# i27_adapt.net
KiCad netlist of a schematic drawn in EAGLE
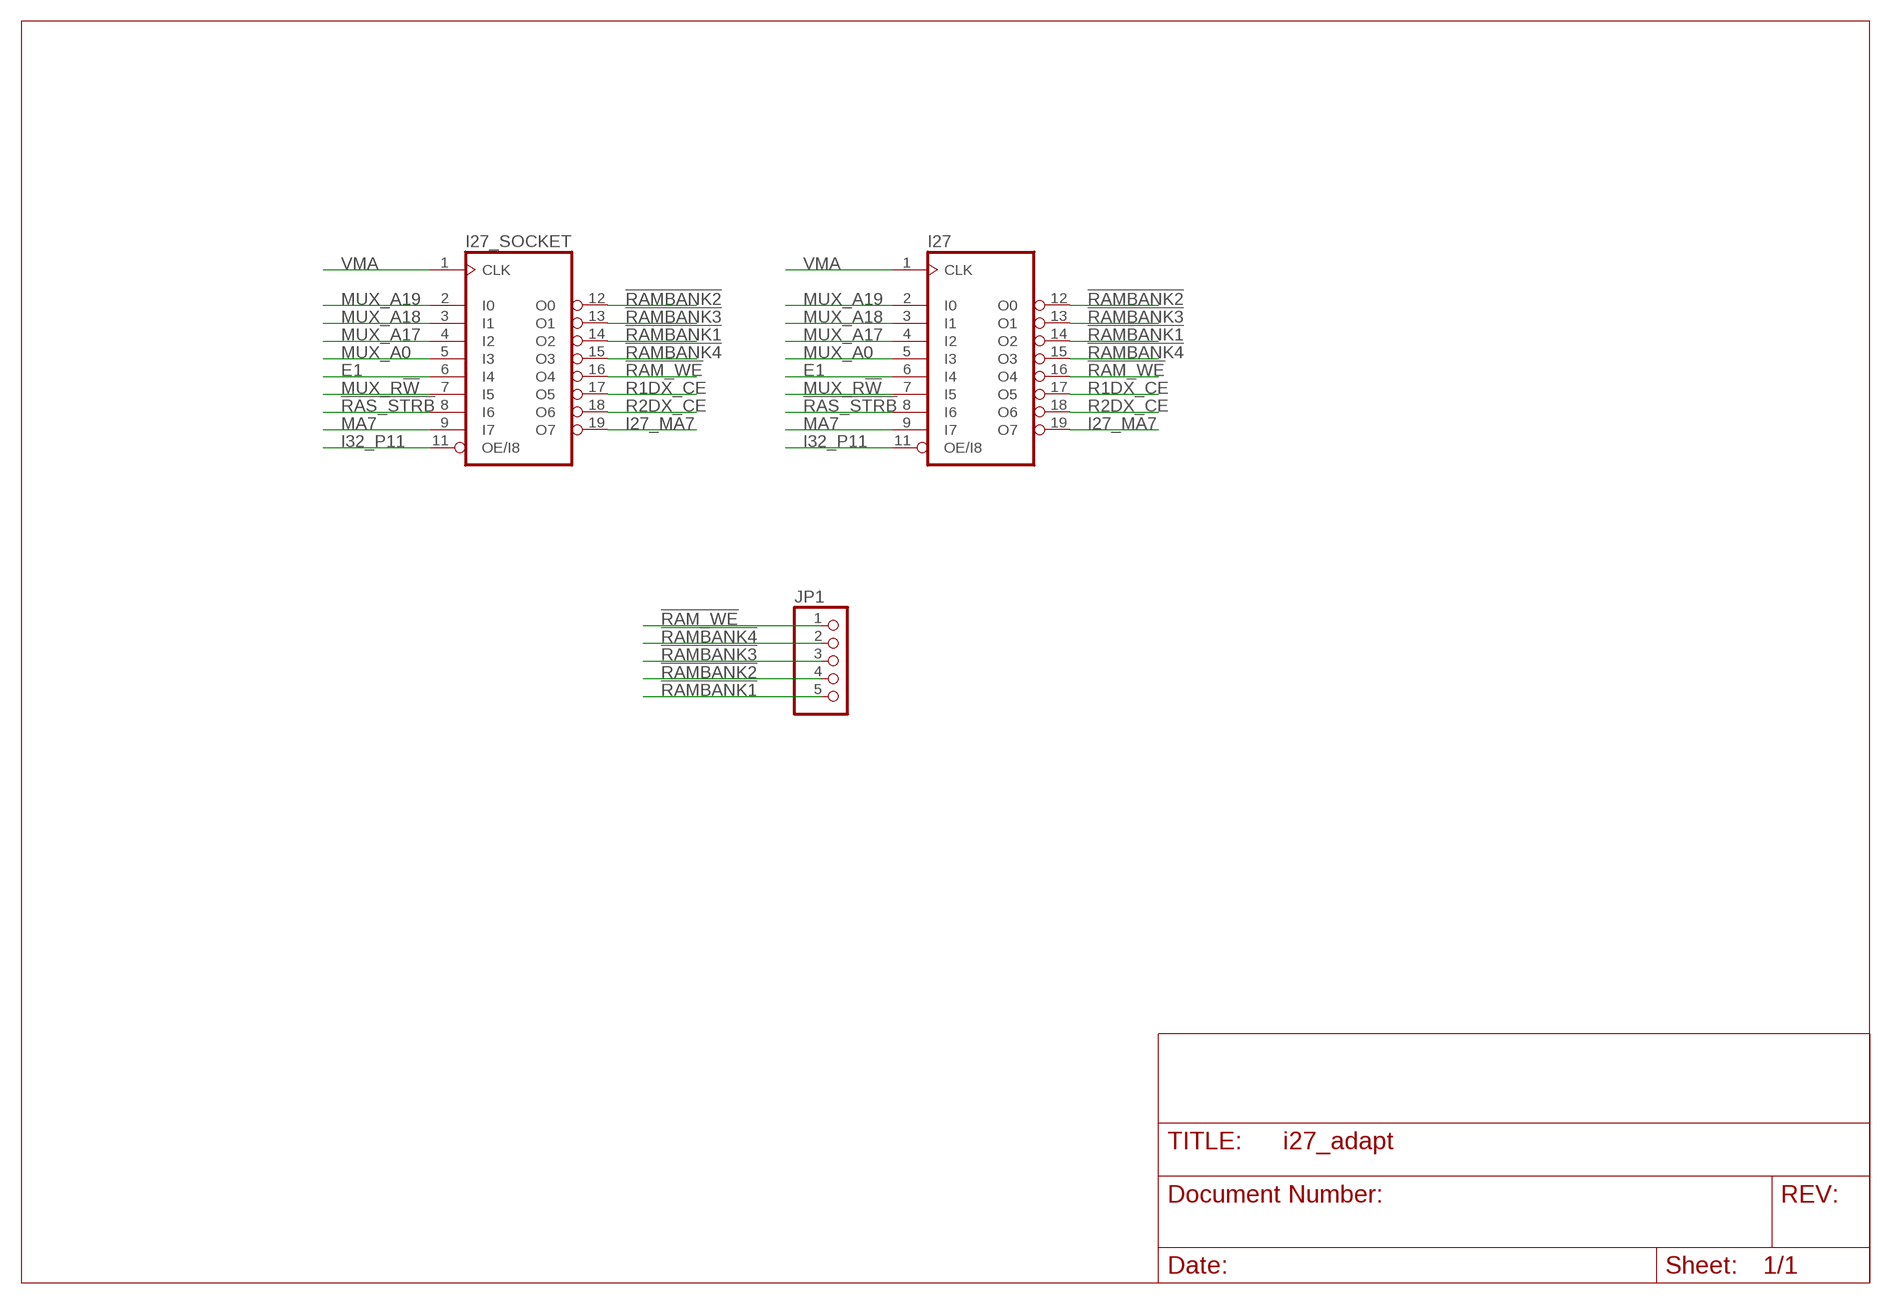
[diagram p0: schematic, sheet 1]

(export (version "E")
  (design (tool "Eeschema 10.0.6"))
  (components
    (comp (ref "I27")
      (value "16V8-ROUND")
      (footprint "eagle-import:DIL20-R")
      (libsource (lib "eagle-import") (part "16V8-ROUND"))
    )
    (comp (ref "I27_SOCKET")
      (value "16V8-ROUND")
      (footprint "eagle-import:DIL20-R")
      (libsource (lib "eagle-import") (part "16V8-ROUND"))
    )
    (comp (ref "JP1")
      (value "PINHD-1X5/90")
      (footprint "eagle-import:1X05_90")
      (libsource (lib "eagle-import") (part "PINHD-1X5/90"))
    )
  )
  (nets
    (net (code "1") (name "/E1") (class "Default")
      (node (ref "I27") (pin "6") (pinfunction "I4_6") (pintype "input"))
      (node (ref "I27_SOCKET") (pin "6") (pinfunction "I4_6") (pintype "input"))
    )
    (net (code "2") (name "/I27_MA7") (class "Default")
      (node (ref "I27") (pin "19") (pinfunction "O7_19") (pintype "bidirectional"))
      (node (ref "I27_SOCKET") (pin "19") (pinfunction "O7_19") (pintype "bidirectional"))
    )
    (net (code "3") (name "/I32_P11") (class "Default")
      (node (ref "I27") (pin "11") (pinfunction "OE/I8_11") (pintype "input"))
      (node (ref "I27_SOCKET") (pin "11") (pinfunction "OE/I8_11") (pintype "input"))
    )
    (net (code "4") (name "/MA7") (class "Default")
      (node (ref "I27") (pin "9") (pinfunction "I7_9") (pintype "input"))
      (node (ref "I27_SOCKET") (pin "9") (pinfunction "I7_9") (pintype "input"))
    )
    (net (code "5") (name "/MUX_A0") (class "Default")
      (node (ref "I27") (pin "5") (pinfunction "I3_5") (pintype "input"))
      (node (ref "I27_SOCKET") (pin "5") (pinfunction "I3_5") (pintype "input"))
    )
    (net (code "6") (name "/MUX_A17") (class "Default")
      (node (ref "I27") (pin "4") (pinfunction "I2_4") (pintype "input"))
      (node (ref "I27_SOCKET") (pin "4") (pinfunction "I2_4") (pintype "input"))
    )
    (net (code "7") (name "/MUX_A18") (class "Default")
      (node (ref "I27") (pin "3") (pinfunction "I1_3") (pintype "input"))
      (node (ref "I27_SOCKET") (pin "3") (pinfunction "I1_3") (pintype "input"))
    )
    (net (code "8") (name "/MUX_A19") (class "Default")
      (node (ref "I27") (pin "2") (pinfunction "I0_2") (pintype "input"))
      (node (ref "I27_SOCKET") (pin "2") (pinfunction "I0_2") (pintype "input"))
    )
    (net (code "9") (name "/MUX_R~{W}") (class "Default")
      (node (ref "I27") (pin "7") (pinfunction "I5_7") (pintype "input"))
      (node (ref "I27_SOCKET") (pin "7") (pinfunction "I5_7") (pintype "input"))
    )
    (net (code "10") (name "/R1DX_CE") (class "Default")
      (node (ref "I27") (pin "17") (pinfunction "O5_17") (pintype "bidirectional"))
      (node (ref "I27_SOCKET") (pin "17") (pinfunction "O5_17") (pintype "bidirectional"))
    )
    (net (code "11") (name "/R2DX_CE") (class "Default")
      (node (ref "I27") (pin "18") (pinfunction "O6_18") (pintype "bidirectional"))
      (node (ref "I27_SOCKET") (pin "18") (pinfunction "O6_18") (pintype "bidirectional"))
    )
    (net (code "12") (name "/VMA") (class "Default")
      (node (ref "I27") (pin "1") (pinfunction "CLK_1") (pintype "input"))
      (node (ref "I27_SOCKET") (pin "1") (pinfunction "CLK_1") (pintype "input"))
    )
    (net (code "13") (name "/~{RAMBANK1}") (class "Default")
      (node (ref "I27") (pin "14") (pinfunction "O2_14") (pintype "bidirectional"))
      (node (ref "I27_SOCKET") (pin "14") (pinfunction "O2_14") (pintype "bidirectional"))
      (node (ref "JP1") (pin "5") (pinfunction "5_5") (pintype "passive"))
    )
    (net (code "14") (name "/~{RAMBANK2}") (class "Default")
      (node (ref "I27") (pin "12") (pinfunction "O0_12") (pintype "bidirectional"))
      (node (ref "I27_SOCKET") (pin "12") (pinfunction "O0_12") (pintype "bidirectional"))
      (node (ref "JP1") (pin "4") (pinfunction "4_4") (pintype "passive"))
    )
    (net (code "15") (name "/~{RAMBANK3}") (class "Default")
      (node (ref "I27") (pin "13") (pinfunction "O1_13") (pintype "bidirectional"))
      (node (ref "I27_SOCKET") (pin "13") (pinfunction "O1_13") (pintype "bidirectional"))
      (node (ref "JP1") (pin "3") (pinfunction "3_3") (pintype "passive"))
    )
    (net (code "16") (name "/~{RAMBANK4}") (class "Default")
      (node (ref "I27") (pin "15") (pinfunction "O3_15") (pintype "bidirectional"))
      (node (ref "I27_SOCKET") (pin "15") (pinfunction "O3_15") (pintype "bidirectional"))
      (node (ref "JP1") (pin "2") (pinfunction "2_2") (pintype "passive"))
    )
    (net (code "17") (name "/~{RAM_WE}") (class "Default")
      (node (ref "I27") (pin "16") (pinfunction "O4_16") (pintype "bidirectional"))
      (node (ref "I27_SOCKET") (pin "16") (pinfunction "O4_16") (pintype "bidirectional"))
      (node (ref "JP1") (pin "1") (pinfunction "1_1") (pintype "passive"))
    )
    (net (code "18") (name "/~{RAS_STRB}") (class "Default")
      (node (ref "I27") (pin "8") (pinfunction "I6_8") (pintype "input"))
      (node (ref "I27_SOCKET") (pin "8") (pinfunction "I6_8") (pintype "input"))
    )
  )
)
